# TDC.net
KiCad netlist of a schematic drawn in Altium Designer
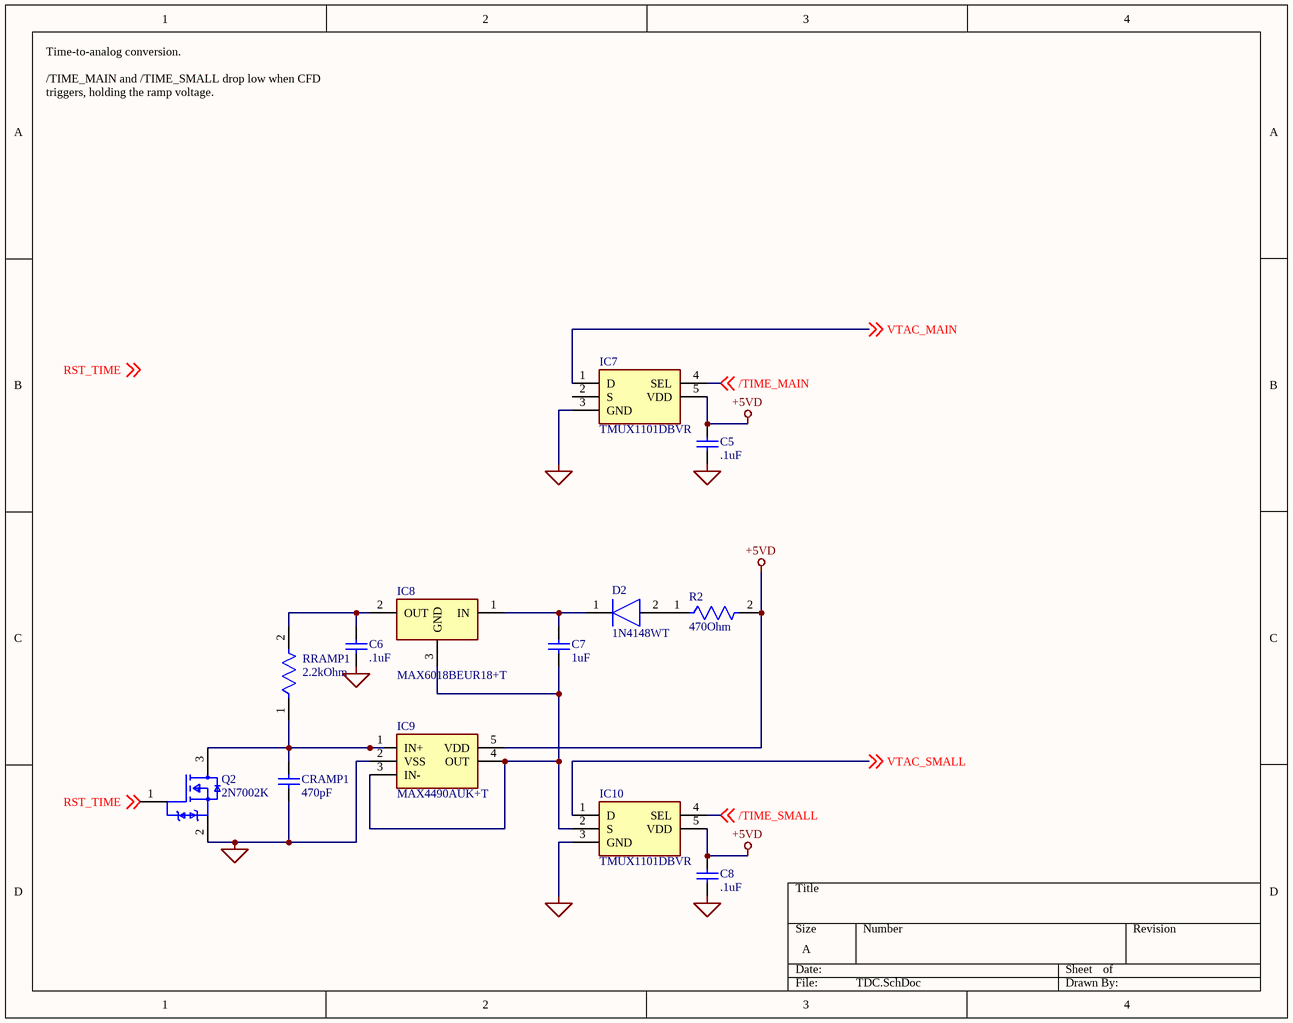
[diagram p0: TDC.SchDoc]

(export (version "E")
  (design (tool "Eeschema 10.0.6"))
  (components
    (comp (ref "C5")
      (value ".1uF")
      (footprint "CAPC2013X140X45NL15T25")
      (description "0402")
      (fields (field (name "PART NUMBER") "GRM21BR71A106KE51L") (field (name "MANUFACTURER") "Murata"))
      (libsource (lib "Altium Content Vault") (part "CAP"))
    )
    (comp (ref "C6")
      (value ".1uF")
      (footprint "CAPC2013X140X45NL15T25")
      (description "0402")
      (fields (field (name "PART NUMBER") "GRM21BR71A106KE51L") (field (name "MANUFACTURER") "Murata"))
      (libsource (lib "Altium Content Vault") (part "CAP"))
    )
    (comp (ref "C7")
      (value "1uF")
      (footprint "CAPC2013X140X45NL15T25")
      (description "0402")
      (fields (field (name "PART NUMBER") "GRM21BR71A106KE51L") (field (name "MANUFACTURER") "Murata"))
      (libsource (lib "Altium Content Vault") (part "CAP"))
    )
    (comp (ref "C8")
      (value ".1uF")
      (footprint "CAPC2013X140X45NL15T25")
      (description "0402")
      (fields (field (name "PART NUMBER") "GRM21BR71A106KE51L") (field (name "MANUFACTURER") "Murata"))
      (libsource (lib "Altium Content Vault") (part "CAP"))
    )
    (comp (ref "CRAMP1")
      (value "470pF")
      (footprint "CAPC2013X140X45NL15T25")
      (description "0402")
      (fields (field (name "PART NUMBER") "GRM21BR71A106KE51L") (field (name "MANUFACTURER") "Murata"))
      (libsource (lib "Altium Content Vault") (part "CAP"))
    )
    (comp (ref "D2")
      (value "1N4148WT")
      (footprint "SamacSys:SODFL1608X70N")
      (description "Diode")
      (libsource (lib "*") (part "1N4148WT"))
    )
    (comp (ref "IC7")
      (value "TMUX1101DBVR")
      (footprint "SamacSys:SOT95P280X145-5N")
      (libsource (lib "*") (part "TMUX1101DBVR"))
    )
    (comp (ref "IC8")
      (value "MAX6018BEUR18+T")
      (footprint "SamacSys:SOT95P237X112-3N")
      (description "Voltage References Precision, Micropower, 1.8V Supply, Low-Dropout, SOT23 Voltage Reference")
      (libsource (lib "SamacSys") (part "MAX6018BEUR18+T"))
    )
    (comp (ref "IC9")
      (value "MAX4490AUK+T")
      (footprint "SamacSys:SOT95P280X145-5N")
      (description "Integrated Circuit")
      (libsource (lib "SamacSys") (part "MAX4490AUK+T"))
    )
    (comp (ref "IC10")
      (value "TMUX1101DBVR")
      (footprint "SamacSys:SOT95P280X145-5N")
      (libsource (lib "*") (part "TMUX1101DBVR"))
    )
    (comp (ref "Q2")
      (value "2N7002K")
      (footprint "FP-318-08-MFG")
      (description "MOSFET N-CH 60V 300MA SOT23")
      (fields
        (field (name "OCTOPART") "https://octopart.com/2n7002k-on+semiconductor-84408900")
        (field (name "MANUFACTURER") "ON Semiconductor")
      )
      (libsource (lib "Altium Content Vault") (part "40bafa8609a25cdbb0dab398ef4a0d9"))
    )
    (comp (ref "R2")
      (value "470Ohm")
      (footprint "FP-CRCW0402-e3-IPC_C")
      (description "RES Thick Film, 0Ω, 0.063W, 0402")
      (fields (field (name "TOLERANCE") "5%"))
      (libsource (lib "Altium Content Vault") (part "1029c3af85768c4190bb7ad29bc67b5"))
    )
    (comp (ref "RRAMP1")
      (value "2.2kOhm")
      (footprint "FP-CRCW0603-e3-MFG")
      (description "RES Thick Film, 1MΩ, 1%, 0.1W, 100ppm/°C, 0603")
      (fields (field (name "TOLERANCE") "1%"))
      (libsource (lib "Altium Content Vault") (part "1029c3af85768c4190bb7ad29bc67b5"))
    )
  )
  (nets
    (net (code "1") (name "+5VD") (class "Default")
      (node (ref "C5") (pin "2") (pinfunction "2_2") (pintype "passive"))
      (node (ref "C8") (pin "2") (pinfunction "2_2") (pintype "passive"))
      (node (ref "IC10") (pin "5") (pinfunction "VDD_5") (pintype "passive"))
      (node (ref "IC7") (pin "5") (pinfunction "VDD_5") (pintype "passive"))
      (node (ref "IC9") (pin "5") (pinfunction "VDD_5") (pintype "passive"))
      (node (ref "R2") (pin "2") (pinfunction "2_2") (pintype "passive"))
    )
    (net (code "2") (name "GND") (class "Default")
      (node (ref "C5") (pin "1") (pinfunction "1_1") (pintype "passive"))
      (node (ref "C6") (pin "1") (pinfunction "1_1") (pintype "passive"))
      (node (ref "C8") (pin "1") (pinfunction "1_1") (pintype "passive"))
      (node (ref "CRAMP1") (pin "1") (pinfunction "1_1") (pintype "passive"))
      (node (ref "IC10") (pin "3") (pinfunction "GND_3") (pintype "passive"))
      (node (ref "IC7") (pin "3") (pinfunction "GND_3") (pintype "passive"))
      (node (ref "IC9") (pin "2") (pinfunction "VSS_2") (pintype "passive"))
      (node (ref "Q2") (pin "2") (pinfunction "Source_2") (pintype "passive"))
    )
    (net (code "3") (name "Net-(D2-A)") (class "Default")
      (node (ref "D2") (pin "2") (pinfunction "A_2") (pintype "passive"))
      (node (ref "R2") (pin "1") (pinfunction "1_1") (pintype "passive"))
    )
    (net (code "4") (name "Net-(D2-K)") (class "Default")
      (node (ref "C7") (pin "2") (pinfunction "2_2") (pintype "passive"))
      (node (ref "D2") (pin "1") (pinfunction "K_1") (pintype "passive"))
      (node (ref "IC8") (pin "1") (pinfunction "IN_1") (pintype "passive"))
    )
    (net (code "5") (name "Net-(IC8-OUT)") (class "Default")
      (node (ref "C6") (pin "2") (pinfunction "2_2") (pintype "passive"))
      (node (ref "IC8") (pin "2") (pinfunction "OUT_2") (pintype "passive"))
      (node (ref "RRAMP1") (pin "2") (pinfunction "2_2") (pintype "passive"))
    )
    (net (code "6") (name "Net-(IC9-IN+)") (class "Default")
      (node (ref "CRAMP1") (pin "2") (pinfunction "2_2") (pintype "passive"))
      (node (ref "IC9") (pin "1") (pinfunction "IN+_1") (pintype "passive"))
      (node (ref "Q2") (pin "3") (pinfunction "Drain_3") (pintype "passive"))
      (node (ref "RRAMP1") (pin "1") (pinfunction "1_1") (pintype "passive"))
    )
    (net (code "7") (name "Net-(IC10-S)") (class "Default")
      (node (ref "C7") (pin "1") (pinfunction "1_1") (pintype "passive"))
      (node (ref "IC10") (pin "2") (pinfunction "S_2") (pintype "passive"))
      (node (ref "IC8") (pin "3") (pinfunction "GND_3") (pintype "passive"))
      (node (ref "IC9") (pin "3") (pinfunction "IN-_3") (pintype "passive"))
      (node (ref "IC9") (pin "4") (pinfunction "OUT_4") (pintype "passive"))
    )
    (net (code "8") (name "RST_TIME") (class "Default")
      (node (ref "Q2") (pin "1") (pinfunction "Gate_1") (pintype "passive"))
    )
    (net (code "9") (name "VTAC_MAIN") (class "Default")
      (node (ref "IC7") (pin "1") (pinfunction "D_1") (pintype "passive"))
    )
    (net (code "10") (name "VTAC_SMALL") (class "Default")
      (node (ref "IC10") (pin "1") (pinfunction "D_1") (pintype "passive"))
    )
    (net (code "11") (name "unconnected-(IC7-S-Pad2)") (class "Default")
      (node (ref "IC7") (pin "2") (pinfunction "S_2") (pintype "passive"))
    )
    (net (code "12") (name "{slash}TIME_MAIN") (class "Default")
      (node (ref "IC7") (pin "4") (pinfunction "SEL_4") (pintype "passive"))
    )
    (net (code "13") (name "{slash}TIME_SMALL") (class "Default")
      (node (ref "IC10") (pin "4") (pinfunction "SEL_4") (pintype "passive"))
    )
  )
)
